# GPS_Ant_1575.net
KiCad netlist of a schematic drawn in EAGLE
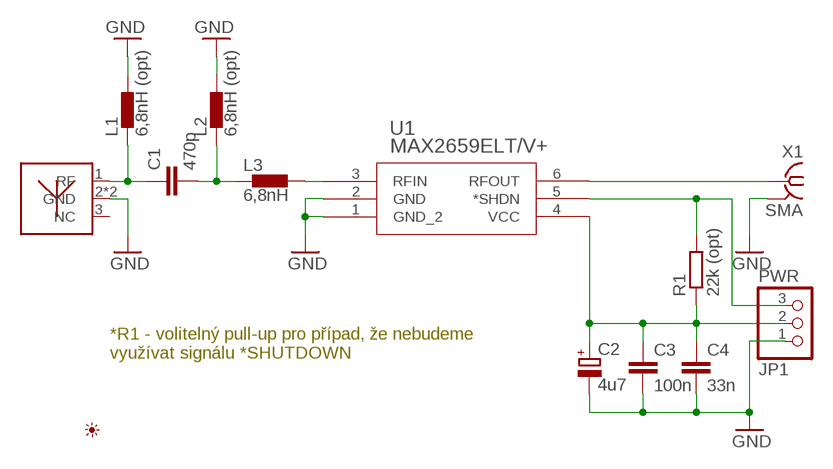
[diagram p0: schematic, sheet 1]

(export (version "E")
  (design (tool "Eeschema 10.0.6"))
  (components
    (comp (ref "ANT1")
      (value "1575AT54A0010")
      (footprint "eagle-import:1575AT54A0010")
      (libsource (lib "eagle-import") (part "1575AT54A0010"))
    )
    (comp (ref "C1")
      (value "470p")
      (footprint "eagle-import:C0603")
      (libsource (lib "eagle-import") (part "C-EUC0603"))
    )
    (comp (ref "C2")
      (value "4u7")
      (footprint "eagle-import:SMC_A")
      (libsource (lib "eagle-import") (part "CPOL-EUSMCA"))
    )
    (comp (ref "C3")
      (value "100n")
      (footprint "eagle-import:C0603")
      (libsource (lib "eagle-import") (part "C-EUC0603"))
    )
    (comp (ref "C4")
      (value "33n")
      (footprint "eagle-import:C0603")
      (libsource (lib "eagle-import") (part "C-EUC0603"))
    )
    (comp (ref "JP1")
      (value "PWR")
      (footprint "eagle-import:1X03")
      (libsource (lib "eagle-import") (part "PINHD-1X3"))
    )
    (comp (ref "L1")
      (value "6,8nH (opt)")
      (footprint "eagle-import:0402")
      (libsource (lib "eagle-import") (part "BLM15HB121SN1"))
    )
    (comp (ref "L2")
      (value "6,8nH (opt)")
      (footprint "eagle-import:0402")
      (libsource (lib "eagle-import") (part "BLM15HB121SN1"))
    )
    (comp (ref "L3")
      (value "6,8nH")
      (footprint "eagle-import:0402")
      (libsource (lib "eagle-import") (part "BLM15HB121SN1"))
    )
    (comp (ref "PICTO1")
      (value "PICTO_1")
      (footprint "eagle-import:PICTO_1")
      (libsource (lib "eagle-import") (part "PICTO_1"))
    )
    (comp (ref "R1")
      (value "22k (opt)")
      (footprint "eagle-import:R0603")
      (libsource (lib "eagle-import") (part "R-EU_R0603"))
    )
    (comp (ref "U1")
      (value "MAX2659ELT/V+")
      (footprint "eagle-import:21-0147E")
      (libsource (lib "eagle-import") (part "MAX2659ELT/V+"))
    )
    (comp (ref "X1")
      (value "SMA")
      (footprint "eagle-import:J502-ND-142-0701-801_806")
      (fields (field (name "MF") "JOHNSON COMPONENTS") (field (name "MPN") "142-0701-801"))
      (libsource (lib "eagle-import") (part "SMA-142-0701-801/806"))
    )
  )
  (nets
    (net (code "1") (name "GND") (class "Default")
      (node (ref "ANT1") (pin "2") (pinfunction "GND_2") (pintype "power_in"))
      (node (ref "ANT1") (pin "4") (pinfunction "GND_4") (pintype "power_in"))
      (node (ref "C2") (pin "-") (pinfunction "-_-") (pintype "passive"))
      (node (ref "C3") (pin "2") (pinfunction "2_2") (pintype "passive"))
      (node (ref "C4") (pin "2") (pinfunction "2_2") (pintype "passive"))
      (node (ref "JP1") (pin "1") (pinfunction "1_1") (pintype "passive"))
      (node (ref "L1") (pin "2") (pinfunction "2_2") (pintype "passive"))
      (node (ref "L2") (pin "2") (pinfunction "2_2") (pintype "passive"))
      (node (ref "U1") (pin "1") (pinfunction "GND_2_1") (pintype "power_in"))
      (node (ref "U1") (pin "2") (pinfunction "GND_2") (pintype "power_in"))
      (node (ref "X1") (pin "G@1") (pinfunction "2_G@1") (pintype "passive"))
      (node (ref "X1") (pin "G@2") (pinfunction "2_G@2") (pintype "passive"))
      (node (ref "X1") (pin "G@3") (pinfunction "2_G@3") (pintype "passive"))
      (node (ref "X1") (pin "G@4") (pinfunction "2_G@4") (pintype "passive"))
    )
    (net (code "2") (name "Net-(ANT1-RF)") (class "Default")
      (node (ref "ANT1") (pin "1") (pinfunction "RF_1") (pintype "output"))
      (node (ref "C1") (pin "1") (pinfunction "1_1") (pintype "passive"))
      (node (ref "L1") (pin "1") (pinfunction "1_1") (pintype "passive"))
    )
    (net (code "3") (name "Net-(C1-Pad2)") (class "Default")
      (node (ref "C1") (pin "2") (pinfunction "2_2") (pintype "passive"))
      (node (ref "L2") (pin "1") (pinfunction "1_1") (pintype "passive"))
      (node (ref "L3") (pin "1") (pinfunction "1_1") (pintype "passive"))
    )
    (net (code "4") (name "Net-(U1-*SHDN)") (class "Default")
      (node (ref "JP1") (pin "3") (pinfunction "3_3") (pintype "passive"))
      (node (ref "R1") (pin "2") (pinfunction "2_2") (pintype "passive"))
      (node (ref "U1") (pin "5") (pinfunction "*SHDN_5") (pintype "passive"))
    )
    (net (code "5") (name "Net-(U1-RFIN)") (class "Default")
      (node (ref "L3") (pin "2") (pinfunction "2_2") (pintype "passive"))
      (node (ref "U1") (pin "3") (pinfunction "RFIN_3") (pintype "input"))
    )
    (net (code "6") (name "Net-(U1-RFOUT)") (class "Default")
      (node (ref "U1") (pin "6") (pinfunction "RFOUT_6") (pintype "output"))
      (node (ref "X1") (pin "1") (pinfunction "1_1") (pintype "passive"))
    )
    (net (code "7") (name "Net-(U1-VCC)") (class "Default")
      (node (ref "C2") (pin "+") (pinfunction "+_+") (pintype "passive"))
      (node (ref "C3") (pin "1") (pinfunction "1_1") (pintype "passive"))
      (node (ref "C4") (pin "1") (pinfunction "1_1") (pintype "passive"))
      (node (ref "JP1") (pin "2") (pinfunction "2_2") (pintype "passive"))
      (node (ref "R1") (pin "1") (pinfunction "1_1") (pintype "passive"))
      (node (ref "U1") (pin "4") (pinfunction "VCC_4") (pintype "power_in"))
    )
    (net (code "8") (name "unconnected-(ANT1-NC-Pad3)") (class "Default")
      (node (ref "ANT1") (pin "3") (pinfunction "NC_3") (pintype "no_connect"))
    )
  )
)
